# ADS8588S.net
KiCad netlist of a schematic drawn in EAGLE
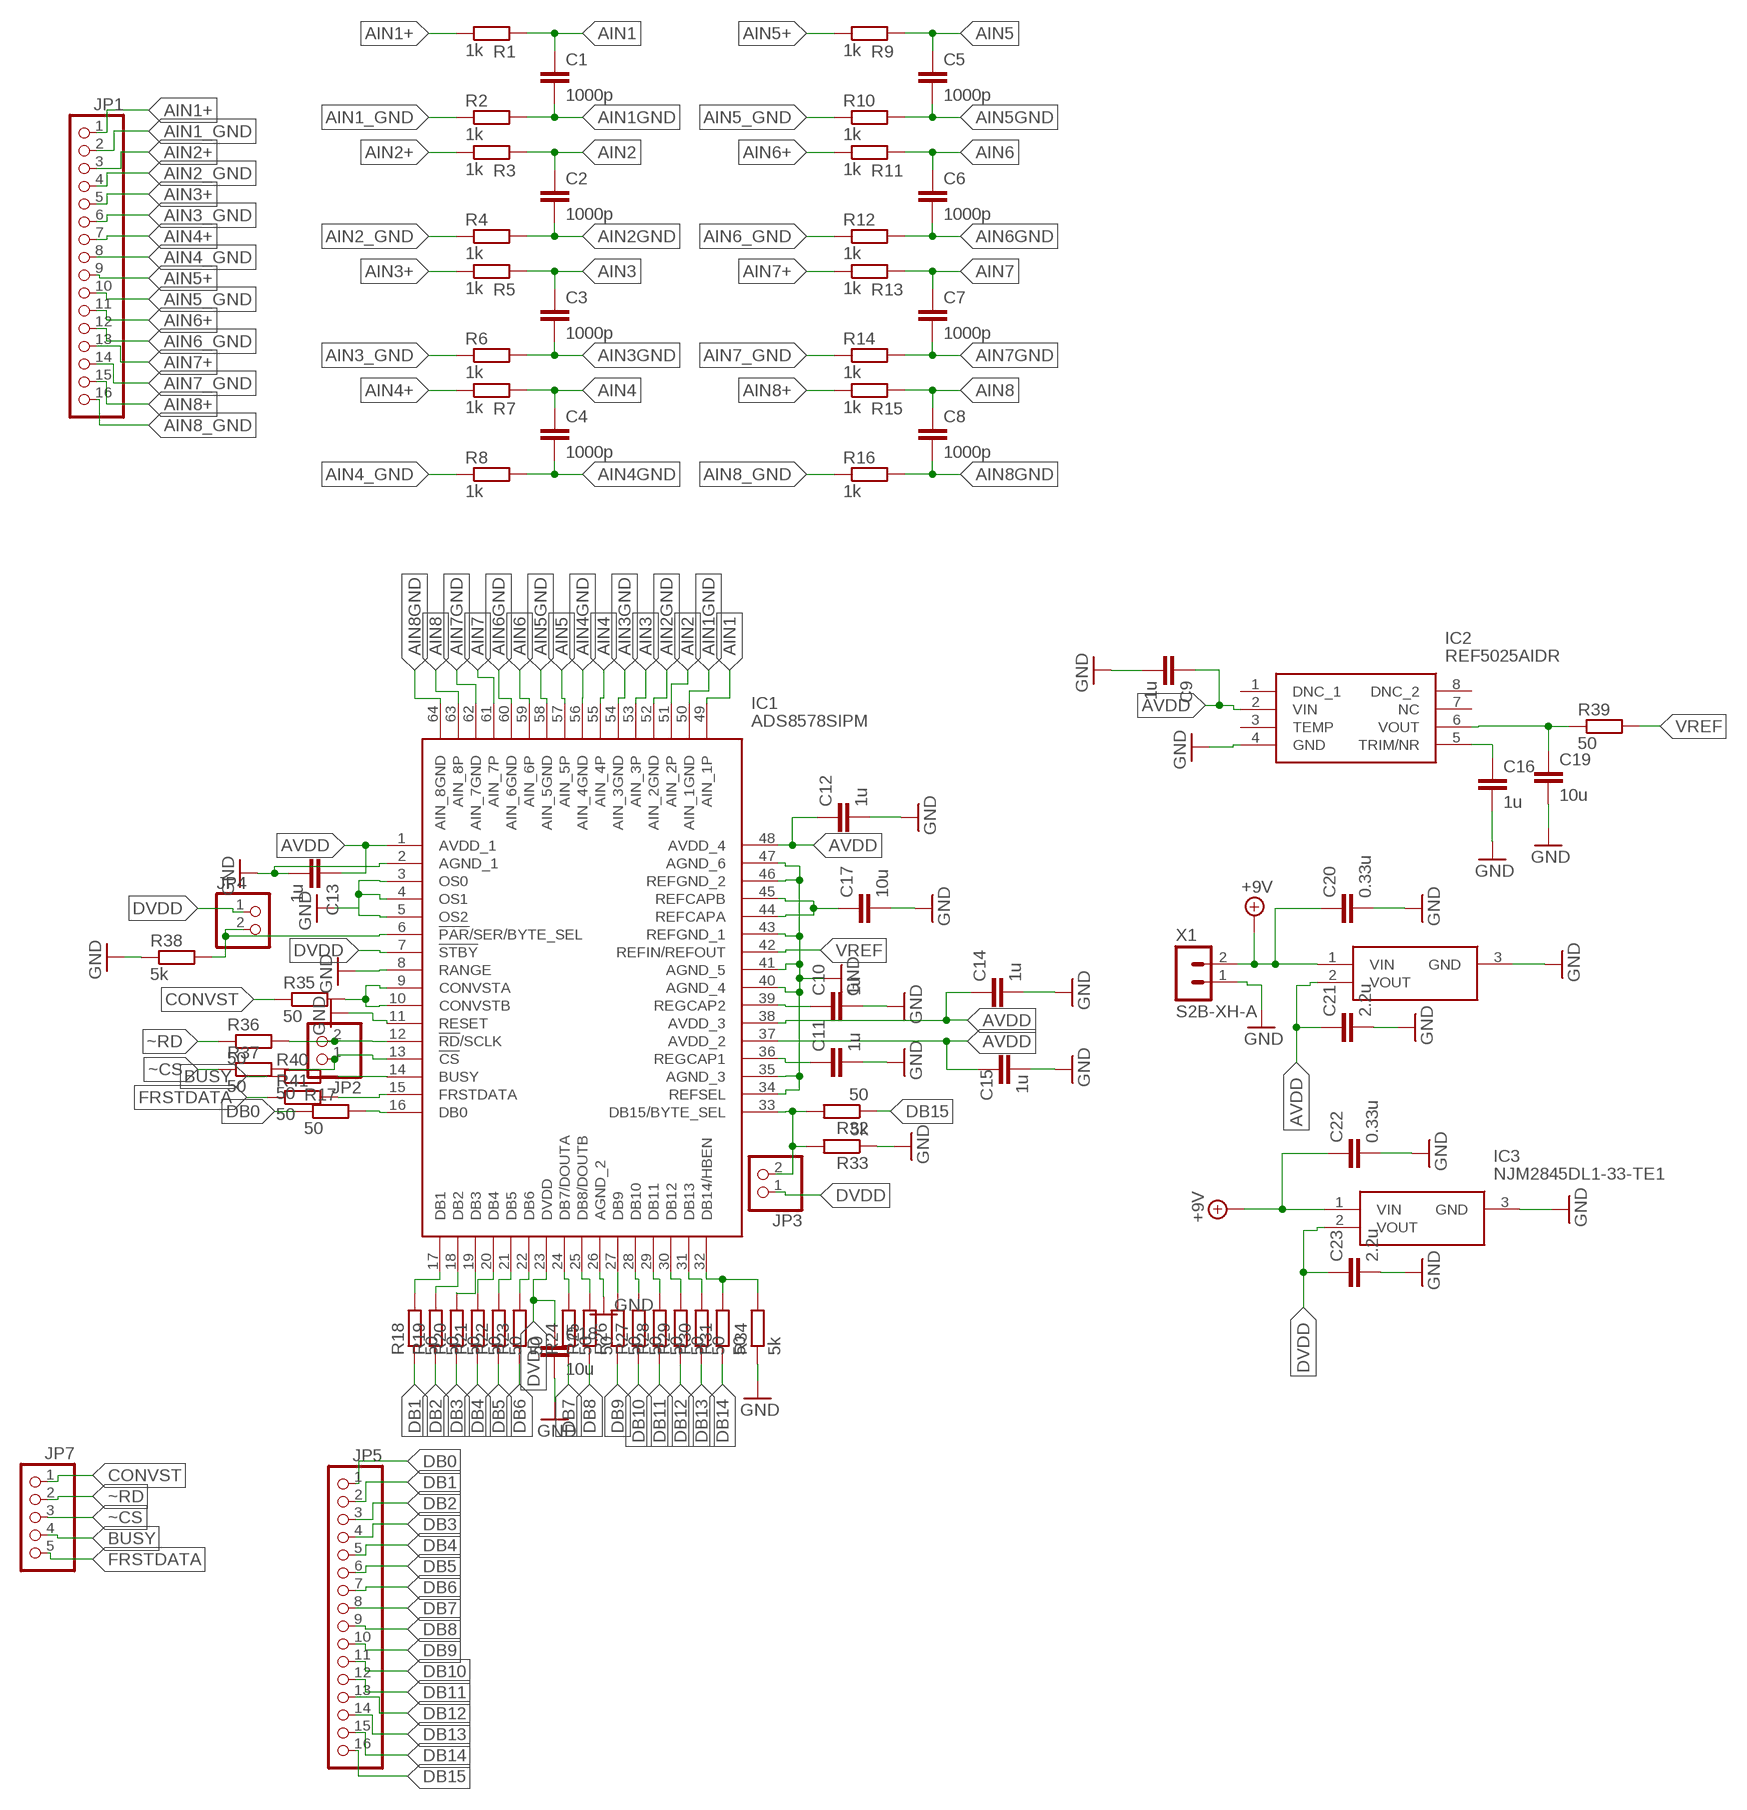
[diagram p0: schematic, sheet 1]

(export (version "E")
  (design (tool "Eeschema 10.0.6"))
  (components
    (comp (ref "C1")
      (value "1000p")
      (footprint "eagle-import:C0603K")
      (libsource (lib "eagle-import") (part "C-EUC0603K"))
    )
    (comp (ref "C2")
      (value "1000p")
      (footprint "eagle-import:C0603K")
      (libsource (lib "eagle-import") (part "C-EUC0603K"))
    )
    (comp (ref "C3")
      (value "1000p")
      (footprint "eagle-import:C0603K")
      (libsource (lib "eagle-import") (part "C-EUC0603K"))
    )
    (comp (ref "C4")
      (value "1000p")
      (footprint "eagle-import:C0603K")
      (libsource (lib "eagle-import") (part "C-EUC0603K"))
    )
    (comp (ref "C5")
      (value "1000p")
      (footprint "eagle-import:C0603K")
      (libsource (lib "eagle-import") (part "C-EUC0603K"))
    )
    (comp (ref "C6")
      (value "1000p")
      (footprint "eagle-import:C0603K")
      (libsource (lib "eagle-import") (part "C-EUC0603K"))
    )
    (comp (ref "C7")
      (value "1000p")
      (footprint "eagle-import:C0603K")
      (libsource (lib "eagle-import") (part "C-EUC0603K"))
    )
    (comp (ref "C8")
      (value "1000p")
      (footprint "eagle-import:C0603K")
      (libsource (lib "eagle-import") (part "C-EUC0603K"))
    )
    (comp (ref "C9")
      (value "1u")
      (footprint "eagle-import:C0603K")
      (libsource (lib "eagle-import") (part "C-EUC0603K"))
    )
    (comp (ref "C10")
      (value "1u")
      (footprint "eagle-import:C0603K")
      (libsource (lib "eagle-import") (part "C-EUC0603K"))
    )
    (comp (ref "C11")
      (value "1u")
      (footprint "eagle-import:C0603K")
      (libsource (lib "eagle-import") (part "C-EUC0603K"))
    )
    (comp (ref "C12")
      (value "1u")
      (footprint "eagle-import:C0603K")
      (libsource (lib "eagle-import") (part "C-EUC0603K"))
    )
    (comp (ref "C13")
      (value "1u")
      (footprint "eagle-import:C0603K")
      (libsource (lib "eagle-import") (part "C-EUC0603K"))
    )
    (comp (ref "C14")
      (value "1u")
      (footprint "eagle-import:C0603K")
      (libsource (lib "eagle-import") (part "C-EUC0603K"))
    )
    (comp (ref "C15")
      (value "1u")
      (footprint "eagle-import:C0603K")
      (libsource (lib "eagle-import") (part "C-EUC0603K"))
    )
    (comp (ref "C16")
      (value "1u")
      (footprint "eagle-import:C0603K")
      (libsource (lib "eagle-import") (part "C-EUC0603K"))
    )
    (comp (ref "C17")
      (value "10u")
      (footprint "eagle-import:C0805K")
      (libsource (lib "eagle-import") (part "C-EUC0805K"))
    )
    (comp (ref "C18")
      (value "10u")
      (footprint "eagle-import:C0805K")
      (libsource (lib "eagle-import") (part "C-EUC0805K"))
    )
    (comp (ref "C19")
      (value "10u")
      (footprint "eagle-import:C0805K")
      (libsource (lib "eagle-import") (part "C-EUC0805K"))
    )
    (comp (ref "C20")
      (value "0.33u")
      (footprint "eagle-import:C0603K")
      (libsource (lib "eagle-import") (part "C-EUC0603K"))
    )
    (comp (ref "C21")
      (value "2.2u")
      (footprint "eagle-import:C0805K")
      (libsource (lib "eagle-import") (part "C-EUC0805K"))
    )
    (comp (ref "C22")
      (value "0.33u")
      (footprint "eagle-import:C0603K")
      (libsource (lib "eagle-import") (part "C-EUC0603K"))
    )
    (comp (ref "C23")
      (value "2.2u")
      (footprint "eagle-import:C0805K")
      (libsource (lib "eagle-import") (part "C-EUC0805K"))
    )
    (comp (ref "IC1")
      (value "ADS8578SIPM")
      (footprint "eagle-import:QFP50P1200X1200X160-64N")
      (fields (field (name "MOUSER_PART_NUMBER") "595-ADS8578SIPM"))
      (libsource (lib "eagle-import") (part "ADS8578SIPM"))
    )
    (comp (ref "IC2")
      (value "REF5025AIDR")
      (footprint "eagle-import:SOIC127P600X175-8N")
      (fields (field (name "MOUSER_PART_NUMBER") "595-REF5025AIDR"))
      (libsource (lib "eagle-import") (part "REF5025AIDR"))
    )
    (comp (ref "IC3")
      (value "NJM2845DL1-33-TE1")
      (footprint "eagle-import:TO-252-3-L1")
      (fields (field (name "MOUSER_PART_NUMBER") "513-NJM2845DL133-TE1"))
      (libsource (lib "eagle-import") (part "NJM2845DL1-33-TE1"))
    )
    (comp (ref "IC5")
      (value "NJM2845DL1-05-TE1")
      (footprint "eagle-import:TO-252-3-L1")
      (fields (field (name "MOUSER_PART_NUMBER") "513-NJM2845DL105-TE1"))
      (libsource (lib "eagle-import") (part "NJM2845DL1-05-TE1"))
    )
    (comp (ref "JP1")
      (value "PINHD-1X16")
      (footprint "eagle-import:1X16")
      (libsource (lib "eagle-import") (part "PINHD-1X16"))
    )
    (comp (ref "JP2")
      (value "PINHD-1X2")
      (footprint "eagle-import:1X02")
      (libsource (lib "eagle-import") (part "PINHD-1X2"))
    )
    (comp (ref "JP3")
      (value "PINHD-1X2")
      (footprint "eagle-import:1X02")
      (libsource (lib "eagle-import") (part "PINHD-1X2"))
    )
    (comp (ref "JP4")
      (value "PINHD-1X2")
      (footprint "eagle-import:1X02")
      (libsource (lib "eagle-import") (part "PINHD-1X2"))
    )
    (comp (ref "JP5")
      (value "PINHD-1X16")
      (footprint "eagle-import:1X16")
      (libsource (lib "eagle-import") (part "PINHD-1X16"))
    )
    (comp (ref "JP7")
      (value "PINHD-1X5")
      (footprint "eagle-import:1X05")
      (libsource (lib "eagle-import") (part "PINHD-1X5"))
    )
    (comp (ref "R1")
      (value "1k")
      (footprint "eagle-import:R0603")
      (libsource (lib "eagle-import") (part "R-EU_R0603"))
    )
    (comp (ref "R2")
      (value "1k")
      (footprint "eagle-import:R0603")
      (libsource (lib "eagle-import") (part "R-EU_R0603"))
    )
    (comp (ref "R3")
      (value "1k")
      (footprint "eagle-import:R0603")
      (libsource (lib "eagle-import") (part "R-EU_R0603"))
    )
    (comp (ref "R4")
      (value "1k")
      (footprint "eagle-import:R0603")
      (libsource (lib "eagle-import") (part "R-EU_R0603"))
    )
    (comp (ref "R5")
      (value "1k")
      (footprint "eagle-import:R0603")
      (libsource (lib "eagle-import") (part "R-EU_R0603"))
    )
    (comp (ref "R6")
      (value "1k")
      (footprint "eagle-import:R0603")
      (libsource (lib "eagle-import") (part "R-EU_R0603"))
    )
    (comp (ref "R7")
      (value "1k")
      (footprint "eagle-import:R0603")
      (libsource (lib "eagle-import") (part "R-EU_R0603"))
    )
    (comp (ref "R8")
      (value "1k")
      (footprint "eagle-import:R0603")
      (libsource (lib "eagle-import") (part "R-EU_R0603"))
    )
    (comp (ref "R9")
      (value "1k")
      (footprint "eagle-import:R0603")
      (libsource (lib "eagle-import") (part "R-EU_R0603"))
    )
    (comp (ref "R10")
      (value "1k")
      (footprint "eagle-import:R0603")
      (libsource (lib "eagle-import") (part "R-EU_R0603"))
    )
    (comp (ref "R11")
      (value "1k")
      (footprint "eagle-import:R0603")
      (libsource (lib "eagle-import") (part "R-EU_R0603"))
    )
    (comp (ref "R12")
      (value "1k")
      (footprint "eagle-import:R0603")
      (libsource (lib "eagle-import") (part "R-EU_R0603"))
    )
    (comp (ref "R13")
      (value "1k")
      (footprint "eagle-import:R0603")
      (libsource (lib "eagle-import") (part "R-EU_R0603"))
    )
    (comp (ref "R14")
      (value "1k")
      (footprint "eagle-import:R0603")
      (libsource (lib "eagle-import") (part "R-EU_R0603"))
    )
    (comp (ref "R15")
      (value "1k")
      (footprint "eagle-import:R0603")
      (libsource (lib "eagle-import") (part "R-EU_R0603"))
    )
    (comp (ref "R16")
      (value "1k")
      (footprint "eagle-import:R0603")
      (libsource (lib "eagle-import") (part "R-EU_R0603"))
    )
    (comp (ref "R17")
      (value "50")
      (footprint "eagle-import:R0603")
      (libsource (lib "eagle-import") (part "R-EU_R0603"))
    )
    (comp (ref "R18")
      (value "50")
      (footprint "eagle-import:R0603")
      (libsource (lib "eagle-import") (part "R-EU_R0603"))
    )
    (comp (ref "R19")
      (value "50")
      (footprint "eagle-import:R0603")
      (libsource (lib "eagle-import") (part "R-EU_R0603"))
    )
    (comp (ref "R20")
      (value "50")
      (footprint "eagle-import:R0603")
      (libsource (lib "eagle-import") (part "R-EU_R0603"))
    )
    (comp (ref "R21")
      (value "50")
      (footprint "eagle-import:R0603")
      (libsource (lib "eagle-import") (part "R-EU_R0603"))
    )
    (comp (ref "R22")
      (value "50")
      (footprint "eagle-import:R0603")
      (libsource (lib "eagle-import") (part "R-EU_R0603"))
    )
    (comp (ref "R23")
      (value "50")
      (footprint "eagle-import:R0603")
      (libsource (lib "eagle-import") (part "R-EU_R0603"))
    )
    (comp (ref "R24")
      (value "50")
      (footprint "eagle-import:R0603")
      (libsource (lib "eagle-import") (part "R-EU_R0603"))
    )
    (comp (ref "R25")
      (value "50")
      (footprint "eagle-import:R0603")
      (libsource (lib "eagle-import") (part "R-EU_R0603"))
    )
    (comp (ref "R26")
      (value "50")
      (footprint "eagle-import:R0603")
      (libsource (lib "eagle-import") (part "R-EU_R0603"))
    )
    (comp (ref "R27")
      (value "50")
      (footprint "eagle-import:R0603")
      (libsource (lib "eagle-import") (part "R-EU_R0603"))
    )
    (comp (ref "R28")
      (value "50")
      (footprint "eagle-import:R0603")
      (libsource (lib "eagle-import") (part "R-EU_R0603"))
    )
    (comp (ref "R29")
      (value "50")
      (footprint "eagle-import:R0603")
      (libsource (lib "eagle-import") (part "R-EU_R0603"))
    )
    (comp (ref "R30")
      (value "50")
      (footprint "eagle-import:R0603")
      (libsource (lib "eagle-import") (part "R-EU_R0603"))
    )
    (comp (ref "R31")
      (value "50")
      (footprint "eagle-import:R0603")
      (libsource (lib "eagle-import") (part "R-EU_R0603"))
    )
    (comp (ref "R32")
      (value "50")
      (footprint "eagle-import:R0603")
      (libsource (lib "eagle-import") (part "R-EU_R0603"))
    )
    (comp (ref "R33")
      (value "5k")
      (footprint "eagle-import:R0603")
      (libsource (lib "eagle-import") (part "R-EU_R0603"))
    )
    (comp (ref "R34")
      (value "5k")
      (footprint "eagle-import:R0603")
      (libsource (lib "eagle-import") (part "R-EU_R0603"))
    )
    (comp (ref "R35")
      (value "50")
      (footprint "eagle-import:R0603")
      (libsource (lib "eagle-import") (part "R-EU_R0603"))
    )
    (comp (ref "R36")
      (value "50")
      (footprint "eagle-import:R0603")
      (libsource (lib "eagle-import") (part "R-EU_R0603"))
    )
    (comp (ref "R37")
      (value "50")
      (footprint "eagle-import:R0603")
      (libsource (lib "eagle-import") (part "R-EU_R0603"))
    )
    (comp (ref "R38")
      (value "5k")
      (footprint "eagle-import:R0603")
      (libsource (lib "eagle-import") (part "R-EU_R0603"))
    )
    (comp (ref "R39")
      (value "50")
      (footprint "eagle-import:R0603")
      (libsource (lib "eagle-import") (part "R-EU_R0603"))
    )
    (comp (ref "R40")
      (value "50")
      (footprint "eagle-import:R0603")
      (libsource (lib "eagle-import") (part "R-EU_R0603"))
    )
    (comp (ref "R41")
      (value "50")
      (footprint "eagle-import:R0603")
      (libsource (lib "eagle-import") (part "R-EU_R0603"))
    )
    (comp (ref "X1")
      (value "S2B-XH-A")
      (footprint "eagle-import:S2B-XH-A")
      (libsource (lib "eagle-import") (part "S2B-XH-A"))
    )
  )
  (nets
    (net (code "1") (name "+9V") (class "Default")
      (node (ref "C20") (pin "1") (pinfunction "1_1") (pintype "passive"))
      (node (ref "C22") (pin "1") (pinfunction "1_1") (pintype "passive"))
      (node (ref "IC3") (pin "1") (pinfunction "VIN_1") (pintype "bidirectional"))
      (node (ref "IC5") (pin "1") (pinfunction "VIN_1") (pintype "bidirectional"))
      (node (ref "X1") (pin "2") (pinfunction "2_2") (pintype "passive"))
    )
    (net (code "2") (name "/~{CS}") (class "Default")
      (node (ref "JP7") (pin "3") (pinfunction "3_3") (pintype "passive"))
      (node (ref "R37") (pin "1") (pinfunction "1_1") (pintype "passive"))
    )
    (net (code "3") (name "/~{RD}") (class "Default")
      (node (ref "JP7") (pin "2") (pinfunction "2_2") (pintype "passive"))
      (node (ref "R36") (pin "1") (pinfunction "1_1") (pintype "passive"))
    )
    (net (code "4") (name "AIN1") (class "Default")
      (node (ref "C1") (pin "1") (pinfunction "1_1") (pintype "passive"))
      (node (ref "IC1") (pin "49") (pinfunction "AIN_1P_49") (pintype "bidirectional"))
      (node (ref "R1") (pin "2") (pinfunction "2_2") (pintype "passive"))
    )
    (net (code "5") (name "AIN1+") (class "Default")
      (node (ref "JP1") (pin "1") (pinfunction "1_1") (pintype "passive"))
      (node (ref "R1") (pin "1") (pinfunction "1_1") (pintype "passive"))
    )
    (net (code "6") (name "AIN1GND") (class "Default")
      (node (ref "C1") (pin "2") (pinfunction "2_2") (pintype "passive"))
      (node (ref "IC1") (pin "50") (pinfunction "AIN_1GND_50") (pintype "bidirectional"))
      (node (ref "R2") (pin "2") (pinfunction "2_2") (pintype "passive"))
    )
    (net (code "7") (name "AIN1_GND") (class "Default")
      (node (ref "JP1") (pin "2") (pinfunction "2_2") (pintype "passive"))
      (node (ref "R2") (pin "1") (pinfunction "1_1") (pintype "passive"))
    )
    (net (code "8") (name "AIN2") (class "Default")
      (node (ref "C2") (pin "1") (pinfunction "1_1") (pintype "passive"))
      (node (ref "IC1") (pin "51") (pinfunction "AIN_2P_51") (pintype "bidirectional"))
      (node (ref "R3") (pin "2") (pinfunction "2_2") (pintype "passive"))
    )
    (net (code "9") (name "AIN2+") (class "Default")
      (node (ref "JP1") (pin "3") (pinfunction "3_3") (pintype "passive"))
      (node (ref "R3") (pin "1") (pinfunction "1_1") (pintype "passive"))
    )
    (net (code "10") (name "AIN2GND") (class "Default")
      (node (ref "C2") (pin "2") (pinfunction "2_2") (pintype "passive"))
      (node (ref "IC1") (pin "52") (pinfunction "AIN_2GND_52") (pintype "bidirectional"))
      (node (ref "R4") (pin "2") (pinfunction "2_2") (pintype "passive"))
    )
    (net (code "11") (name "AIN2_GND") (class "Default")
      (node (ref "JP1") (pin "4") (pinfunction "4_4") (pintype "passive"))
      (node (ref "R4") (pin "1") (pinfunction "1_1") (pintype "passive"))
    )
    (net (code "12") (name "AIN3") (class "Default")
      (node (ref "C3") (pin "1") (pinfunction "1_1") (pintype "passive"))
      (node (ref "IC1") (pin "53") (pinfunction "AIN_3P_53") (pintype "bidirectional"))
      (node (ref "R5") (pin "2") (pinfunction "2_2") (pintype "passive"))
    )
    (net (code "13") (name "AIN3+") (class "Default")
      (node (ref "JP1") (pin "5") (pinfunction "5_5") (pintype "passive"))
      (node (ref "R5") (pin "1") (pinfunction "1_1") (pintype "passive"))
    )
    (net (code "14") (name "AIN3GND") (class "Default")
      (node (ref "C3") (pin "2") (pinfunction "2_2") (pintype "passive"))
      (node (ref "IC1") (pin "54") (pinfunction "AIN_3GND_54") (pintype "bidirectional"))
      (node (ref "R6") (pin "2") (pinfunction "2_2") (pintype "passive"))
    )
    (net (code "15") (name "AIN3_GND") (class "Default")
      (node (ref "JP1") (pin "6") (pinfunction "6_6") (pintype "passive"))
      (node (ref "R6") (pin "1") (pinfunction "1_1") (pintype "passive"))
    )
    (net (code "16") (name "AIN4") (class "Default")
      (node (ref "C4") (pin "1") (pinfunction "1_1") (pintype "passive"))
      (node (ref "IC1") (pin "55") (pinfunction "AIN_4P_55") (pintype "bidirectional"))
      (node (ref "R7") (pin "2") (pinfunction "2_2") (pintype "passive"))
    )
    (net (code "17") (name "AIN4+") (class "Default")
      (node (ref "JP1") (pin "7") (pinfunction "7_7") (pintype "passive"))
      (node (ref "R7") (pin "1") (pinfunction "1_1") (pintype "passive"))
    )
    (net (code "18") (name "AIN4GND") (class "Default")
      (node (ref "C4") (pin "2") (pinfunction "2_2") (pintype "passive"))
      (node (ref "IC1") (pin "56") (pinfunction "AIN_4GND_56") (pintype "bidirectional"))
      (node (ref "R8") (pin "2") (pinfunction "2_2") (pintype "passive"))
    )
    (net (code "19") (name "AIN4_GND") (class "Default")
      (node (ref "JP1") (pin "8") (pinfunction "8_8") (pintype "passive"))
      (node (ref "R8") (pin "1") (pinfunction "1_1") (pintype "passive"))
    )
    (net (code "20") (name "AIN5") (class "Default")
      (node (ref "C5") (pin "1") (pinfunction "1_1") (pintype "passive"))
      (node (ref "IC1") (pin "57") (pinfunction "AIN_5P_57") (pintype "bidirectional"))
      (node (ref "R9") (pin "2") (pinfunction "2_2") (pintype "passive"))
    )
    (net (code "21") (name "AIN5+") (class "Default")
      (node (ref "JP1") (pin "9") (pinfunction "9_9") (pintype "passive"))
      (node (ref "R9") (pin "1") (pinfunction "1_1") (pintype "passive"))
    )
    (net (code "22") (name "AIN5GND") (class "Default")
      (node (ref "C5") (pin "2") (pinfunction "2_2") (pintype "passive"))
      (node (ref "IC1") (pin "58") (pinfunction "AIN_5GND_58") (pintype "bidirectional"))
      (node (ref "R10") (pin "2") (pinfunction "2_2") (pintype "passive"))
    )
    (net (code "23") (name "AIN5_GND") (class "Default")
      (node (ref "JP1") (pin "10") (pinfunction "10_10") (pintype "passive"))
      (node (ref "R10") (pin "1") (pinfunction "1_1") (pintype "passive"))
    )
    (net (code "24") (name "AIN6") (class "Default")
      (node (ref "C6") (pin "1") (pinfunction "1_1") (pintype "passive"))
      (node (ref "IC1") (pin "59") (pinfunction "AIN_6P_59") (pintype "bidirectional"))
      (node (ref "R11") (pin "2") (pinfunction "2_2") (pintype "passive"))
    )
    (net (code "25") (name "AIN6+") (class "Default")
      (node (ref "JP1") (pin "11") (pinfunction "11_11") (pintype "passive"))
      (node (ref "R11") (pin "1") (pinfunction "1_1") (pintype "passive"))
    )
    (net (code "26") (name "AIN6GND") (class "Default")
      (node (ref "C6") (pin "2") (pinfunction "2_2") (pintype "passive"))
      (node (ref "IC1") (pin "60") (pinfunction "AIN_6GND_60") (pintype "bidirectional"))
      (node (ref "R12") (pin "2") (pinfunction "2_2") (pintype "passive"))
    )
    (net (code "27") (name "AIN6_GND") (class "Default")
      (node (ref "JP1") (pin "12") (pinfunction "12_12") (pintype "passive"))
      (node (ref "R12") (pin "1") (pinfunction "1_1") (pintype "passive"))
    )
    (net (code "28") (name "AIN7") (class "Default")
      (node (ref "C7") (pin "1") (pinfunction "1_1") (pintype "passive"))
      (node (ref "IC1") (pin "61") (pinfunction "AIN_7P_61") (pintype "bidirectional"))
      (node (ref "R13") (pin "2") (pinfunction "2_2") (pintype "passive"))
    )
    (net (code "29") (name "AIN7+") (class "Default")
      (node (ref "JP1") (pin "13") (pinfunction "13_13") (pintype "passive"))
      (node (ref "R13") (pin "1") (pinfunction "1_1") (pintype "passive"))
    )
    (net (code "30") (name "AIN7GND") (class "Default")
      (node (ref "C7") (pin "2") (pinfunction "2_2") (pintype "passive"))
      (node (ref "IC1") (pin "62") (pinfunction "AIN_7GND_62") (pintype "bidirectional"))
      (node (ref "R14") (pin "2") (pinfunction "2_2") (pintype "passive"))
    )
    (net (code "31") (name "AIN7_GND") (class "Default")
      (node (ref "JP1") (pin "14") (pinfunction "14_14") (pintype "passive"))
      (node (ref "R14") (pin "1") (pinfunction "1_1") (pintype "passive"))
    )
    (net (code "32") (name "AIN8") (class "Default")
      (node (ref "C8") (pin "1") (pinfunction "1_1") (pintype "passive"))
      (node (ref "IC1") (pin "63") (pinfunction "AIN_8P_63") (pintype "bidirectional"))
      (node (ref "R15") (pin "2") (pinfunction "2_2") (pintype "passive"))
    )
    (net (code "33") (name "AIN8+") (class "Default")
      (node (ref "JP1") (pin "15") (pinfunction "15_15") (pintype "passive"))
      (node (ref "R15") (pin "1") (pinfunction "1_1") (pintype "passive"))
    )
    (net (code "34") (name "AIN8GND") (class "Default")
      (node (ref "C8") (pin "2") (pinfunction "2_2") (pintype "passive"))
      (node (ref "IC1") (pin "64") (pinfunction "AIN_8GND_64") (pintype "bidirectional"))
      (node (ref "R16") (pin "2") (pinfunction "2_2") (pintype "passive"))
    )
    (net (code "35") (name "AIN8_GND") (class "Default")
      (node (ref "JP1") (pin "16") (pinfunction "16_16") (pintype "passive"))
      (node (ref "R16") (pin "1") (pinfunction "1_1") (pintype "passive"))
    )
    (net (code "36") (name "AVDD") (class "Default")
      (node (ref "C12") (pin "1") (pinfunction "1_1") (pintype "passive"))
      (node (ref "C13") (pin "1") (pinfunction "1_1") (pintype "passive"))
      (node (ref "C14") (pin "1") (pinfunction "1_1") (pintype "passive"))
      (node (ref "C15") (pin "1") (pinfunction "1_1") (pintype "passive"))
      (node (ref "C21") (pin "1") (pinfunction "1_1") (pintype "passive"))
      (node (ref "C9") (pin "1") (pinfunction "1_1") (pintype "passive"))
      (node (ref "IC1") (pin "1") (pinfunction "AVDD_1_1") (pintype "bidirectional"))
      (node (ref "IC1") (pin "37") (pinfunction "AVDD_2_37") (pintype "bidirectional"))
      (node (ref "IC1") (pin "38") (pinfunction "AVDD_3_38") (pintype "bidirectional"))
      (node (ref "IC1") (pin "48") (pinfunction "AVDD_4_48") (pintype "bidirectional"))
      (node (ref "IC2") (pin "2") (pinfunction "VIN_2") (pintype "bidirectional"))
      (node (ref "IC5") (pin "2") (pinfunction "VOUT_2") (pintype "bidirectional"))
    )
    (net (code "37") (name "BUSY") (class "Default")
      (node (ref "JP7") (pin "4") (pinfunction "4_4") (pintype "passive"))
      (node (ref "R40") (pin "1") (pinfunction "1_1") (pintype "passive"))
    )
    (net (code "38") (name "CONVST") (class "Default")
      (node (ref "JP7") (pin "1") (pinfunction "1_1") (pintype "passive"))
      (node (ref "R35") (pin "1") (pinfunction "1_1") (pintype "passive"))
    )
    (net (code "39") (name "DB0") (class "Default")
      (node (ref "JP5") (pin "1") (pinfunction "1_1") (pintype "passive"))
      (node (ref "R17") (pin "1") (pinfunction "1_1") (pintype "passive"))
    )
    (net (code "40") (name "DB1") (class "Default")
      (node (ref "JP5") (pin "2") (pinfunction "2_2") (pintype "passive"))
      (node (ref "R18") (pin "1") (pinfunction "1_1") (pintype "passive"))
    )
    (net (code "41") (name "DB2") (class "Default")
      (node (ref "JP5") (pin "3") (pinfunction "3_3") (pintype "passive"))
      (node (ref "R19") (pin "1") (pinfunction "1_1") (pintype "passive"))
    )
    (net (code "42") (name "DB3") (class "Default")
      (node (ref "JP5") (pin "4") (pinfunction "4_4") (pintype "passive"))
      (node (ref "R20") (pin "1") (pinfunction "1_1") (pintype "passive"))
    )
    (net (code "43") (name "DB4") (class "Default")
      (node (ref "JP5") (pin "5") (pinfunction "5_5") (pintype "passive"))
      (node (ref "R21") (pin "1") (pinfunction "1_1") (pintype "passive"))
    )
    (net (code "44") (name "DB5") (class "Default")
      (node (ref "JP5") (pin "6") (pinfunction "6_6") (pintype "passive"))
      (node (ref "R22") (pin "1") (pinfunction "1_1") (pintype "passive"))
    )
    (net (code "45") (name "DB6") (class "Default")
      (node (ref "JP5") (pin "7") (pinfunction "7_7") (pintype "passive"))
      (node (ref "R23") (pin "1") (pinfunction "1_1") (pintype "passive"))
    )
    (net (code "46") (name "DB7") (class "Default")
      (node (ref "JP5") (pin "8") (pinfunction "8_8") (pintype "passive"))
      (node (ref "R24") (pin "1") (pinfunction "1_1") (pintype "passive"))
    )
    (net (code "47") (name "DB8") (class "Default")
      (node (ref "JP5") (pin "9") (pinfunction "9_9") (pintype "passive"))
      (node (ref "R25") (pin "1") (pinfunction "1_1") (pintype "passive"))
    )
    (net (code "48") (name "DB9") (class "Default")
      (node (ref "JP5") (pin "10") (pinfunction "10_10") (pintype "passive"))
      (node (ref "R26") (pin "1") (pinfunction "1_1") (pintype "passive"))
    )
    (net (code "49") (name "DB10") (class "Default")
      (node (ref "JP5") (pin "11") (pinfunction "11_11") (pintype "passive"))
      (node (ref "R27") (pin "1") (pinfunction "1_1") (pintype "passive"))
    )
    (net (code "50") (name "DB11") (class "Default")
      (node (ref "JP5") (pin "12") (pinfunction "12_12") (pintype "passive"))
      (node (ref "R28") (pin "1") (pinfunction "1_1") (pintype "passive"))
    )
    (net (code "51") (name "DB12") (class "Default")
      (node (ref "JP5") (pin "13") (pinfunction "13_13") (pintype "passive"))
      (node (ref "R29") (pin "1") (pinfunction "1_1") (pintype "passive"))
    )
    (net (code "52") (name "DB13") (class "Default")
      (node (ref "JP5") (pin "14") (pinfunction "14_14") (pintype "passive"))
      (node (ref "R30") (pin "1") (pinfunction "1_1") (pintype "passive"))
    )
    (net (code "53") (name "DB14") (class "Default")
      (node (ref "JP5") (pin "15") (pinfunction "15_15") (pintype "passive"))
      (node (ref "R31") (pin "1") (pinfunction "1_1") (pintype "passive"))
    )
    (net (code "54") (name "DB15") (class "Default")
      (node (ref "JP5") (pin "16") (pinfunction "16_16") (pintype "passive"))
      (node (ref "R32") (pin "1") (pinfunction "1_1") (pintype "passive"))
    )
    (net (code "55") (name "DVDD") (class "Default")
      (node (ref "C18") (pin "1") (pinfunction "1_1") (pintype "passive"))
      (node (ref "C23") (pin "1") (pinfunction "1_1") (pintype "passive"))
      (node (ref "IC1") (pin "23") (pinfunction "DVDD_23") (pintype "bidirectional"))
      (node (ref "IC1") (pin "7") (pinfunction "~{STBY}_7") (pintype "bidirectional"))
      (node (ref "IC3") (pin "2") (pinfunction "VOUT_2") (pintype "bidirectional"))
      (node (ref "JP3") (pin "1") (pinfunction "1_1") (pintype "passive"))
      (node (ref "JP4") (pin "1") (pinfunction "1_1") (pintype "passive"))
    )
    (net (code "56") (name "FRSTDATA") (class "Default")
      (node (ref "JP7") (pin "5") (pinfunction "5_5") (pintype "passive"))
      (node (ref "R41") (pin "1") (pinfunction "1_1") (pintype "passive"))
    )
    (net (code "57") (name "GND") (class "Default")
      (node (ref "C10") (pin "2") (pinfunction "2_2") (pintype "passive"))
      (node (ref "C11") (pin "2") (pinfunction "2_2") (pintype "passive"))
      (node (ref "C12") (pin "2") (pinfunction "2_2") (pintype "passive"))
      (node (ref "C13") (pin "2") (pinfunction "2_2") (pintype "passive"))
      (node (ref "C14") (pin "2") (pinfunction "2_2") (pintype "passive"))
      (node (ref "C15") (pin "2") (pinfunction "2_2") (pintype "passive"))
      (node (ref "C16") (pin "2") (pinfunction "2_2") (pintype "passive"))
      (node (ref "C17") (pin "2") (pinfunction "2_2") (pintype "passive"))
      (node (ref "C18") (pin "2") (pinfunction "2_2") (pintype "passive"))
      (node (ref "C19") (pin "2") (pinfunction "2_2") (pintype "passive"))
      (node (ref "C20") (pin "2") (pinfunction "2_2") (pintype "passive"))
      (node (ref "C21") (pin "2") (pinfunction "2_2") (pintype "passive"))
      (node (ref "C22") (pin "2") (pinfunction "2_2") (pintype "passive"))
      (node (ref "C23") (pin "2") (pinfunction "2_2") (pintype "passive"))
      (node (ref "C9") (pin "2") (pinfunction "2_2") (pintype "passive"))
      (node (ref "IC1") (pin "11") (pinfunction "RESET_11") (pintype "bidirectional"))
      (node (ref "IC1") (pin "2") (pinfunction "AGND_1_2") (pintype "bidirectional"))
      (node (ref "IC1") (pin "26") (pinfunction "AGND_2_26") (pintype "bidirectional"))
      (node (ref "IC1") (pin "3") (pinfunction "OS0_3") (pintype "bidirectional"))
      (node (ref "IC1") (pin "34") (pinfunction "REFSEL_34") (pintype "bidirectional"))
      (node (ref "IC1") (pin "35") (pinfunction "AGND_3_35") (pintype "bidirectional"))
      (node (ref "IC1") (pin "4") (pinfunction "OS1_4") (pintype "bidirectional"))
      (node (ref "IC1") (pin "40") (pinfunction "AGND_4_40") (pintype "bidirectional"))
      (node (ref "IC1") (pin "41") (pinfunction "AGND_5_41") (pintype "bidirectional"))
      (node (ref "IC1") (pin "43") (pinfunction "REFGND_1_43") (pintype "bidirectional"))
      (node (ref "IC1") (pin "46") (pinfunction "REFGND_2_46") (pintype "bidirectional"))
      (node (ref "IC1") (pin "47") (pinfunction "AGND_6_47") (pintype "bidirectional"))
      (node (ref "IC1") (pin "5") (pinfunction "OS2_5") (pintype "bidirectional"))
      (node (ref "IC1") (pin "8") (pinfunction "RANGE_8") (pintype "bidirectional"))
      (node (ref "IC2") (pin "4") (pinfunction "GND_4") (pintype "bidirectional"))
      (node (ref "IC3") (pin "3") (pinfunction "GND_3") (pintype "bidirectional"))
      (node (ref "IC5") (pin "3") (pinfunction "GND_3") (pintype "bidirectional"))
      (node (ref "R33") (pin "1") (pinfunction "1_1") (pintype "passive"))
      (node (ref "R34") (pin "1") (pinfunction "1_1") (pintype "passive"))
      (node (ref "R38") (pin "1") (pinfunction "1_1") (pintype "passive"))
      (node (ref "X1") (pin "1") (pinfunction "1_1") (pintype "passive"))
    )
    (net (code "58") (name "Net-(IC1-BUSY)") (class "Default")
      (node (ref "IC1") (pin "14") (pinfunction "BUSY_14") (pintype "bidirectional"))
      (node (ref "R40") (pin "2") (pinfunction "2_2") (pintype "passive"))
    )
    (net (code "59") (name "Net-(IC1-CONVSTA)") (class "Default")
      (node (ref "IC1") (pin "10") (pinfunction "CONVSTB_10") (pintype "bidirectional"))
      (node (ref "IC1") (pin "9") (pinfunction "CONVSTA_9") (pintype "bidirectional"))
      (node (ref "R35") (pin "2") (pinfunction "2_2") (pintype "passive"))
    )
    (net (code "60") (name "Net-(IC1-DB0)") (class "Default")
      (node (ref "IC1") (pin "16") (pinfunction "DB0_16") (pintype "bidirectional"))
      (node (ref "R17") (pin "2") (pinfunction "2_2") (pintype "passive"))
    )
    (net (code "61") (name "Net-(IC1-DB1)") (class "Default")
      (node (ref "IC1") (pin "17") (pinfunction "DB1_17") (pintype "bidirectional"))
      (node (ref "R18") (pin "2") (pinfunction "2_2") (pintype "passive"))
    )
    (net (code "62") (name "Net-(IC1-DB2)") (class "Default")
      (node (ref "IC1") (pin "18") (pinfunction "DB2_18") (pintype "bidirectional"))
      (node (ref "R19") (pin "2") (pinfunction "2_2") (pintype "passive"))
    )
    (net (code "63") (name "Net-(IC1-DB3)") (class "Default")
      (node (ref "IC1") (pin "19") (pinfunction "DB3_19") (pintype "bidirectional"))
      (node (ref "R20") (pin "2") (pinfunction "2_2") (pintype "passive"))
    )
    (net (code "64") (name "Net-(IC1-DB4)") (class "Default")
      (node (ref "IC1") (pin "20") (pinfunction "DB4_20") (pintype "bidirectional"))
      (node (ref "R21") (pin "2") (pinfunction "2_2") (pintype "passive"))
    )
    (net (code "65") (name "Net-(IC1-DB5)") (class "Default")
      (node (ref "IC1") (pin "21") (pinfunction "DB5_21") (pintype "bidirectional"))
      (node (ref "R22") (pin "2") (pinfunction "2_2") (pintype "passive"))
    )
    (net (code "66") (name "Net-(IC1-DB6)") (class "Default")
      (node (ref "IC1") (pin "22") (pinfunction "DB6_22") (pintype "bidirectional"))
      (node (ref "R23") (pin "2") (pinfunction "2_2") (pintype "passive"))
    )
    (net (code "67") (name "Net-(IC1-DB7{slash}DOUTA)") (class "Default")
      (node (ref "IC1") (pin "24") (pinfunction "DB7/DOUTA_24") (pintype "bidirectional"))
      (node (ref "R24") (pin "2") (pinfunction "2_2") (pintype "passive"))
    )
    (net (code "68") (name "Net-(IC1-DB8{slash}DOUTB)") (class "Default")
      (node (ref "IC1") (pin "25") (pinfunction "DB8/DOUTB_25") (pintype "bidirectional"))
      (node (ref "R25") (pin "2") (pinfunction "2_2") (pintype "passive"))
    )
    (net (code "69") (name "Net-(IC1-DB9)") (class "Default")
      (node (ref "IC1") (pin "27") (pinfunction "DB9_27") (pintype "bidirectional"))
      (node (ref "R26") (pin "2") (pinfunction "2_2") (pintype "passive"))
    )
    (net (code "70") (name "Net-(IC1-DB10)") (class "Default")
      (node (ref "IC1") (pin "28") (pinfunction "DB10_28") (pintype "bidirectional"))
      (node (ref "R27") (pin "2") (pinfunction "2_2") (pintype "passive"))
    )
    (net (code "71") (name "Net-(IC1-DB11)") (class "Default")
      (node (ref "IC1") (pin "29") (pinfunction "DB11_29") (pintype "bidirectional"))
      (node (ref "R28") (pin "2") (pinfunction "2_2") (pintype "passive"))
    )
    (net (code "72") (name "Net-(IC1-DB12)") (class "Default")
      (node (ref "IC1") (pin "30") (pinfunction "DB12_30") (pintype "bidirectional"))
      (node (ref "R29") (pin "2") (pinfunction "2_2") (pintype "passive"))
    )
    (net (code "73") (name "Net-(IC1-DB13)") (class "Default")
      (node (ref "IC1") (pin "31") (pinfunction "DB13_31") (pintype "bidirectional"))
      (node (ref "R30") (pin "2") (pinfunction "2_2") (pintype "passive"))
    )
    (net (code "74") (name "Net-(IC1-DB14{slash}HBEN)") (class "Default")
      (node (ref "IC1") (pin "32") (pinfunction "DB14/HBEN_32") (pintype "bidirectional"))
      (node (ref "R31") (pin "2") (pinfunction "2_2") (pintype "passive"))
      (node (ref "R34") (pin "2") (pinfunction "2_2") (pintype "passive"))
    )
    (net (code "75") (name "Net-(IC1-DB15{slash}BYTE_SEL)") (class "Default")
      (node (ref "IC1") (pin "33") (pinfunction "DB15/BYTE_SEL_33") (pintype "bidirectional"))
      (node (ref "JP3") (pin "2") (pinfunction "2_2") (pintype "passive"))
      (node (ref "R32") (pin "2") (pinfunction "2_2") (pintype "passive"))
      (node (ref "R33") (pin "2") (pinfunction "2_2") (pintype "passive"))
    )
    (net (code "76") (name "Net-(IC1-FRSTDATA)") (class "Default")
      (node (ref "IC1") (pin "15") (pinfunction "FRSTDATA_15") (pintype "bidirectional"))
      (node (ref "R41") (pin "2") (pinfunction "2_2") (pintype "passive"))
    )
    (net (code "77") (name "Net-(IC1-REFCAPA)") (class "Default")
      (node (ref "C17") (pin "1") (pinfunction "1_1") (pintype "passive"))
      (node (ref "IC1") (pin "44") (pinfunction "REFCAPA_44") (pintype "bidirectional"))
      (node (ref "IC1") (pin "45") (pinfunction "REFCAPB_45") (pintype "bidirectional"))
    )
    (net (code "78") (name "Net-(IC1-REGCAP1)") (class "Default")
      (node (ref "C11") (pin "1") (pinfunction "1_1") (pintype "passive"))
      (node (ref "IC1") (pin "36") (pinfunction "REGCAP1_36") (pintype "bidirectional"))
    )
    (net (code "79") (name "Net-(IC1-REGCAP2)") (class "Default")
      (node (ref "C10") (pin "1") (pinfunction "1_1") (pintype "passive"))
      (node (ref "IC1") (pin "39") (pinfunction "REGCAP2_39") (pintype "bidirectional"))
    )
    (net (code "80") (name "Net-(IC1-~{CS})") (class "Default")
      (node (ref "IC1") (pin "13") (pinfunction "~{CS}_13") (pintype "bidirectional"))
      (node (ref "JP2") (pin "1") (pinfunction "1_1") (pintype "passive"))
      (node (ref "R37") (pin "2") (pinfunction "2_2") (pintype "passive"))
    )
    (net (code "81") (name "Net-(IC1-~{PAR}{slash}SER{slash}BYTE_SEL)") (class "Default")
      (node (ref "IC1") (pin "6") (pinfunction "~{PAR}/SER/BYTE_SEL_6") (pintype "bidirectional"))
      (node (ref "JP4") (pin "2") (pinfunction "2_2") (pintype "passive"))
      (node (ref "R38") (pin "2") (pinfunction "2_2") (pintype "passive"))
    )
    (net (code "82") (name "Net-(IC1-~{RD}{slash}SCLK)") (class "Default")
      (node (ref "IC1") (pin "12") (pinfunction "~{RD}/SCLK_12") (pintype "bidirectional"))
      (node (ref "JP2") (pin "2") (pinfunction "2_2") (pintype "passive"))
      (node (ref "R36") (pin "2") (pinfunction "2_2") (pintype "passive"))
    )
    (net (code "83") (name "Net-(IC2-TRIM{slash}NR)") (class "Default")
      (node (ref "C16") (pin "1") (pinfunction "1_1") (pintype "passive"))
      (node (ref "IC2") (pin "5") (pinfunction "TRIM/NR_5") (pintype "bidirectional"))
    )
    (net (code "84") (name "Net-(IC2-VOUT)") (class "Default")
      (node (ref "C19") (pin "1") (pinfunction "1_1") (pintype "passive"))
      (node (ref "IC2") (pin "6") (pinfunction "VOUT_6") (pintype "bidirectional"))
      (node (ref "R39") (pin "1") (pinfunction "1_1") (pintype "passive"))
    )
    (net (code "85") (name "VREF") (class "Default")
      (node (ref "IC1") (pin "42") (pinfunction "REFIN/REFOUT_42") (pintype "bidirectional"))
      (node (ref "R39") (pin "2") (pinfunction "2_2") (pintype "passive"))
    )
    (net (code "86") (name "unconnected-(IC2-DNC_1-Pad1)") (class "Default")
      (node (ref "IC2") (pin "1") (pinfunction "DNC_1_1") (pintype "bidirectional"))
    )
    (net (code "87") (name "unconnected-(IC2-DNC_2-Pad8)") (class "Default")
      (node (ref "IC2") (pin "8") (pinfunction "DNC_2_8") (pintype "bidirectional"))
    )
    (net (code "88") (name "unconnected-(IC2-NC-Pad7)") (class "Default")
      (node (ref "IC2") (pin "7") (pinfunction "NC_7") (pintype "no_connect"))
    )
    (net (code "89") (name "unconnected-(IC2-TEMP-Pad3)") (class "Default")
      (node (ref "IC2") (pin "3") (pinfunction "TEMP_3") (pintype "bidirectional"))
    )
  )
)
